# CIR_LED_SEQ.net
KiCad netlist of a schematic drawn in Altium Designer
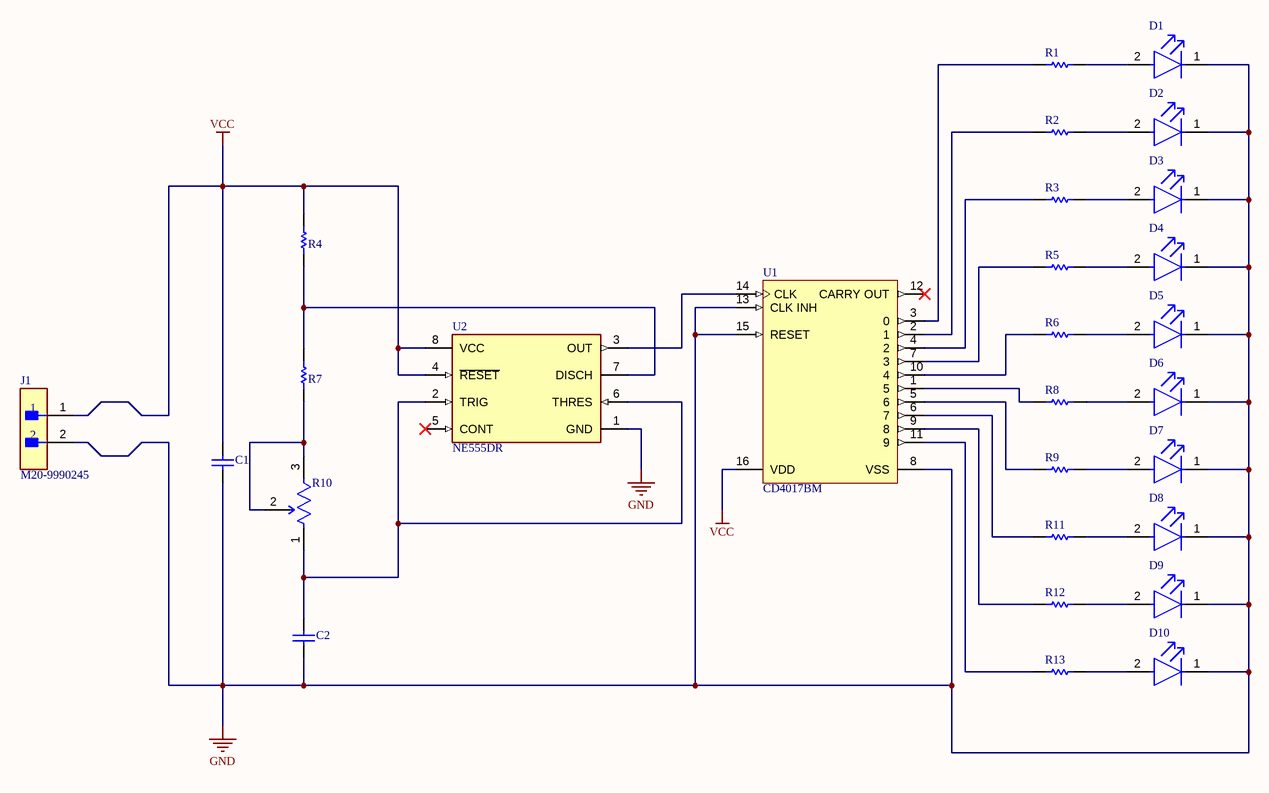
[diagram p0: CIR_LED_SEQ.SchDoc]

(export (version "E")
  (design (tool "Eeschema 10.0.6"))
  (components
    (comp (ref "C1")
      (value "1uf")
      (footprint "CAPC2013X135X45LL10T25")
      (fields (field (name "MANUFACTURER") "Murata") (field (name "PART NUMBER") "GRM21BR71H105KA12L"))
      (libsource (lib "Altium Content Vault") (part "CAP"))
    )
    (comp (ref "C2")
      (value "GRM21BR71H105KA12L")
      (footprint "CAPC2013X135X45LL10T25")
      (fields (field (name "MANUFACTURER") "Murata"))
      (libsource (lib "Altium Content Vault") (part "CAP"))
    )
    (comp (ref "D1")
      (value "HLMP-1719")
      (footprint "FP-HLMP-1719-MFG")
      (description "LED YELLOW DIFFUSED T-1 T/H")
      (fields
        (field (name "MANUFACTURER") "Broadcom")
        (field (name "OCTOPART") "https://octopart.com/hlmp-1719-broadcom-71130405")
      )
      (libsource (lib "Altium Content Vault") (part "8706943c75ba83719d021d2fdc84c58"))
    )
    (comp (ref "D2")
      (value "HLMP-1719")
      (footprint "FP-HLMP-1719-MFG")
      (description "LED YELLOW DIFFUSED T-1 T/H")
      (fields
        (field (name "MANUFACTURER") "Broadcom")
        (field (name "OCTOPART") "https://octopart.com/hlmp-1719-broadcom-71130405")
      )
      (libsource (lib "Altium Content Vault") (part "8706943c75ba83719d021d2fdc84c58"))
    )
    (comp (ref "D3")
      (value "HLMP-1719")
      (footprint "FP-HLMP-1719-MFG")
      (description "LED YELLOW DIFFUSED T-1 T/H")
      (fields
        (field (name "MANUFACTURER") "Broadcom")
        (field (name "OCTOPART") "https://octopart.com/hlmp-1719-broadcom-71130405")
      )
      (libsource (lib "Altium Content Vault") (part "8706943c75ba83719d021d2fdc84c58"))
    )
    (comp (ref "D4")
      (value "HLMP-1719")
      (footprint "FP-HLMP-1719-MFG")
      (description "LED YELLOW DIFFUSED T-1 T/H")
      (fields
        (field (name "MANUFACTURER") "Broadcom")
        (field (name "OCTOPART") "https://octopart.com/hlmp-1719-broadcom-71130405")
      )
      (libsource (lib "Altium Content Vault") (part "8706943c75ba83719d021d2fdc84c58"))
    )
    (comp (ref "D5")
      (value "HLMP-1719")
      (footprint "FP-HLMP-1719-MFG")
      (description "LED YELLOW DIFFUSED T-1 T/H")
      (fields
        (field (name "MANUFACTURER") "Broadcom")
        (field (name "OCTOPART") "https://octopart.com/hlmp-1719-broadcom-71130405")
      )
      (libsource (lib "Altium Content Vault") (part "8706943c75ba83719d021d2fdc84c58"))
    )
    (comp (ref "D6")
      (value "HLMP-1719")
      (footprint "FP-HLMP-1719-MFG")
      (description "LED YELLOW DIFFUSED T-1 T/H")
      (fields
        (field (name "MANUFACTURER") "Broadcom")
        (field (name "OCTOPART") "https://octopart.com/hlmp-1719-broadcom-71130405")
      )
      (libsource (lib "Altium Content Vault") (part "8706943c75ba83719d021d2fdc84c58"))
    )
    (comp (ref "D7")
      (value "HLMP-1719")
      (footprint "FP-HLMP-1719-MFG")
      (description "LED YELLOW DIFFUSED T-1 T/H")
      (fields
        (field (name "MANUFACTURER") "Broadcom")
        (field (name "OCTOPART") "https://octopart.com/hlmp-1719-broadcom-71130405")
      )
      (libsource (lib "Altium Content Vault") (part "8706943c75ba83719d021d2fdc84c58"))
    )
    (comp (ref "D8")
      (value "HLMP-1719")
      (footprint "FP-HLMP-1719-MFG")
      (description "LED YELLOW DIFFUSED T-1 T/H")
      (fields
        (field (name "MANUFACTURER") "Broadcom")
        (field (name "OCTOPART") "https://octopart.com/hlmp-1719-broadcom-71130405")
      )
      (libsource (lib "Altium Content Vault") (part "8706943c75ba83719d021d2fdc84c58"))
    )
    (comp (ref "D9")
      (value "HLMP-1719")
      (footprint "FP-HLMP-1719-MFG")
      (description "LED YELLOW DIFFUSED T-1 T/H")
      (fields
        (field (name "MANUFACTURER") "Broadcom")
        (field (name "OCTOPART") "https://octopart.com/hlmp-1719-broadcom-71130405")
      )
      (libsource (lib "Altium Content Vault") (part "8706943c75ba83719d021d2fdc84c58"))
    )
    (comp (ref "D10")
      (value "HLMP-1719")
      (footprint "FP-HLMP-1719-MFG")
      (description "LED YELLOW DIFFUSED T-1 T/H")
      (fields
        (field (name "MANUFACTURER") "Broadcom")
        (field (name "OCTOPART") "https://octopart.com/hlmp-1719-broadcom-71130405")
      )
      (libsource (lib "Altium Content Vault") (part "8706943c75ba83719d021d2fdc84c58"))
    )
    (comp (ref "J1")
      (value "M20-9990245")
      (footprint "FP-M20-9990245-MFG")
      (description "CONN HEADER VERT 2POS 2.54MM")
      (fields (field (name "VOLTAGE") "50V"))
      (libsource (lib "Altium Content Vault") (part "3bc925449376181038e59eaffc5286c"))
    )
    (comp (ref "R1")
      (value "RC0805FR-071KL")
      (footprint "RESC2013X60X35ML10T20")
      (description "Chip Resistor, 1 KOhm, +/- 1%, 125 mW, -55 to 155 degC, 0805 (2012 Metric), RoHS, Tape and Reel")
      (fields (field (name "TOLERANCE") "1%") (field (name "MANUFACTURER") "Yageo"))
      (libsource (lib "Altium Content Vault") (part "RES-2"))
    )
    (comp (ref "R2")
      (value "RC0805FR-071KL")
      (footprint "RESC2013X60X35ML10T20")
      (description "Chip Resistor, 1 KOhm, +/- 1%, 125 mW, -55 to 155 degC, 0805 (2012 Metric), RoHS, Tape and Reel")
      (fields (field (name "TOLERANCE") "1%") (field (name "MANUFACTURER") "Yageo"))
      (libsource (lib "Altium Content Vault") (part "RES-2"))
    )
    (comp (ref "R3")
      (value "RC0805FR-071KL")
      (footprint "RESC2013X60X35ML10T20")
      (description "Chip Resistor, 1 KOhm, +/- 1%, 125 mW, -55 to 155 degC, 0805 (2012 Metric), RoHS, Tape and Reel")
      (fields (field (name "TOLERANCE") "1%") (field (name "MANUFACTURER") "Yageo"))
      (libsource (lib "Altium Content Vault") (part "RES-2"))
    )
    (comp (ref "R4")
      (value "2k2")
      (footprint "RESC2013X60X35ML10T20")
      (description "Chip Resistor, 1 KOhm, +/- 1%, 125 mW, -55 to 155 degC, 0805 (2012 Metric), RoHS, Tape and Reel")
      (fields (field (name "TOLERANCE") "1%") (field (name "MANUFACTURER") "Yageo"))
      (libsource (lib "Altium Content Vault") (part "RES-2"))
    )
    (comp (ref "R5")
      (value "RC0805FR-071KL")
      (footprint "RESC2013X60X35ML10T20")
      (description "Chip Resistor, 1 KOhm, +/- 1%, 125 mW, -55 to 155 degC, 0805 (2012 Metric), RoHS, Tape and Reel")
      (fields (field (name "TOLERANCE") "1%") (field (name "MANUFACTURER") "Yageo"))
      (libsource (lib "Altium Content Vault") (part "RES-2"))
    )
    (comp (ref "R6")
      (value "RC0805FR-071KL")
      (footprint "RESC2013X60X35ML10T20")
      (description "Chip Resistor, 1 KOhm, +/- 1%, 125 mW, -55 to 155 degC, 0805 (2012 Metric), RoHS, Tape and Reel")
      (fields (field (name "TOLERANCE") "1%") (field (name "MANUFACTURER") "Yageo"))
      (libsource (lib "Altium Content Vault") (part "RES-2"))
    )
    (comp (ref "R7")
      (value "10k")
      (footprint "RESC2013X60X35ML10T20")
      (description "Chip Resistor, 1 KOhm, +/- 1%, 125 mW, -55 to 155 degC, 0805 (2012 Metric), RoHS, Tape and Reel")
      (fields (field (name "TOLERANCE") "1%") (field (name "MANUFACTURER") "Yageo"))
      (libsource (lib "Altium Content Vault") (part "RES-2"))
    )
    (comp (ref "R8")
      (value "RC0805FR-071KL")
      (footprint "RESC2013X60X35ML10T20")
      (description "Chip Resistor, 1 KOhm, +/- 1%, 125 mW, -55 to 155 degC, 0805 (2012 Metric), RoHS, Tape and Reel")
      (fields (field (name "TOLERANCE") "1%") (field (name "MANUFACTURER") "Yageo"))
      (libsource (lib "Altium Content Vault") (part "RES-2"))
    )
    (comp (ref "R9")
      (value "RC0805FR-071KL")
      (footprint "RESC2013X60X35ML10T20")
      (description "Chip Resistor, 1 KOhm, +/- 1%, 125 mW, -55 to 155 degC, 0805 (2012 Metric), RoHS, Tape and Reel")
      (fields (field (name "TOLERANCE") "1%") (field (name "MANUFACTURER") "Yageo"))
      (libsource (lib "Altium Content Vault") (part "RES-2"))
    )
    (comp (ref "R10")
      (value "50k")
      (footprint "FP-3386P-MFG")
      (description "TRIMMER 100K OHM 0.5W PC PIN TOP")
      (fields (field (name "TOLERANCE") "10%"))
      (libsource (lib "Altium Content Vault") (part "13357d81287629c2fd191d242cfa50c"))
    )
    (comp (ref "R11")
      (value "RC0805FR-071KL")
      (footprint "RESC2013X60X35ML10T20")
      (description "Chip Resistor, 1 KOhm, +/- 1%, 125 mW, -55 to 155 degC, 0805 (2012 Metric), RoHS, Tape and Reel")
      (fields (field (name "TOLERANCE") "1%") (field (name "MANUFACTURER") "Yageo"))
      (libsource (lib "Altium Content Vault") (part "RES-2"))
    )
    (comp (ref "R12")
      (value "RC0805FR-071KL")
      (footprint "RESC2013X60X35ML10T20")
      (description "Chip Resistor, 1 KOhm, +/- 1%, 125 mW, -55 to 155 degC, 0805 (2012 Metric), RoHS, Tape and Reel")
      (fields (field (name "TOLERANCE") "1%") (field (name "MANUFACTURER") "Yageo"))
      (libsource (lib "Altium Content Vault") (part "RES-2"))
    )
    (comp (ref "R13")
      (value "RC0805FR-071KL")
      (footprint "RESC2013X60X35ML10T20")
      (description "Chip Resistor, 1 KOhm, +/- 1%, 125 mW, -55 to 155 degC, 0805 (2012 Metric), RoHS, Tape and Reel")
      (fields (field (name "TOLERANCE") "1%") (field (name "MANUFACTURER") "Yageo"))
      (libsource (lib "Altium Content Vault") (part "RES-2"))
    )
    (comp (ref "U1")
      (value "CD4017BM")
      (footprint "D0016A_N")
      (description "CMOS Decade Counter with 10 Decoded Outputs, D0016A, TUBE")
      (fields
        (field (name "GENERIC PART NUMBER") "CD4017B")
        (field (name "MANUFACTURER") "Texas Instruments")
      )
      (libsource (lib "Altium Content Vault") (part "TI-CD4017B-16"))
    )
    (comp (ref "U2")
      (value "NE555DR")
      (footprint "FP-D0008A-IPC_A")
      (description "IC OSC SGL TIMER 100KHZ 8-SOIC")
      (libsource (lib "Altium Content Vault") (part "a29bba90211dec1890110b94dad7d53"))
    )
  )
  (nets
    (net (code "1") (name "GND") (class "Default")
      (node (ref "C1") (pin "1") (pinfunction "1_1") (pintype "passive"))
      (node (ref "C2") (pin "1") (pinfunction "1_1") (pintype "passive"))
      (node (ref "D1") (pin "1") (pinfunction "C_1") (pintype "passive"))
      (node (ref "D10") (pin "1") (pinfunction "C_1") (pintype "passive"))
      (node (ref "D2") (pin "1") (pinfunction "C_1") (pintype "passive"))
      (node (ref "D3") (pin "1") (pinfunction "C_1") (pintype "passive"))
      (node (ref "D4") (pin "1") (pinfunction "C_1") (pintype "passive"))
      (node (ref "D5") (pin "1") (pinfunction "C_1") (pintype "passive"))
      (node (ref "D6") (pin "1") (pinfunction "C_1") (pintype "passive"))
      (node (ref "D7") (pin "1") (pinfunction "C_1") (pintype "passive"))
      (node (ref "D8") (pin "1") (pinfunction "C_1") (pintype "passive"))
      (node (ref "D9") (pin "1") (pinfunction "C_1") (pintype "passive"))
      (node (ref "J1") (pin "2") (pinfunction "2_2") (pintype "passive"))
      (node (ref "U1") (pin "13") (pinfunction "CLK_INH_13") (pintype "input"))
      (node (ref "U1") (pin "15") (pinfunction "RESET_15") (pintype "input"))
      (node (ref "U1") (pin "8") (pinfunction "VSS_8") (pintype "power_in"))
      (node (ref "U2") (pin "1") (pinfunction "GND_1") (pintype "power_in"))
    )
    (net (code "2") (name "Net-(D1-A)") (class "Default")
      (node (ref "D1") (pin "2") (pinfunction "A_2") (pintype "passive"))
      (node (ref "R1") (pin "2") (pinfunction "2_2") (pintype "passive"))
    )
    (net (code "3") (name "Net-(D2-A)") (class "Default")
      (node (ref "D2") (pin "2") (pinfunction "A_2") (pintype "passive"))
      (node (ref "R2") (pin "2") (pinfunction "2_2") (pintype "passive"))
    )
    (net (code "4") (name "Net-(D3-A)") (class "Default")
      (node (ref "D3") (pin "2") (pinfunction "A_2") (pintype "passive"))
      (node (ref "R3") (pin "2") (pinfunction "2_2") (pintype "passive"))
    )
    (net (code "5") (name "Net-(D4-A)") (class "Default")
      (node (ref "D4") (pin "2") (pinfunction "A_2") (pintype "passive"))
      (node (ref "R5") (pin "2") (pinfunction "2_2") (pintype "passive"))
    )
    (net (code "6") (name "Net-(D5-A)") (class "Default")
      (node (ref "D5") (pin "2") (pinfunction "A_2") (pintype "passive"))
      (node (ref "R6") (pin "2") (pinfunction "2_2") (pintype "passive"))
    )
    (net (code "7") (name "Net-(D6-A)") (class "Default")
      (node (ref "D6") (pin "2") (pinfunction "A_2") (pintype "passive"))
      (node (ref "R8") (pin "2") (pinfunction "2_2") (pintype "passive"))
    )
    (net (code "8") (name "Net-(D7-A)") (class "Default")
      (node (ref "D7") (pin "2") (pinfunction "A_2") (pintype "passive"))
      (node (ref "R9") (pin "2") (pinfunction "2_2") (pintype "passive"))
    )
    (net (code "9") (name "Net-(D8-A)") (class "Default")
      (node (ref "D8") (pin "2") (pinfunction "A_2") (pintype "passive"))
      (node (ref "R11") (pin "2") (pinfunction "2_2") (pintype "passive"))
    )
    (net (code "10") (name "Net-(D9-A)") (class "Default")
      (node (ref "D9") (pin "2") (pinfunction "A_2") (pintype "passive"))
      (node (ref "R12") (pin "2") (pinfunction "2_2") (pintype "passive"))
    )
    (net (code "11") (name "Net-(D10-A)") (class "Default")
      (node (ref "D10") (pin "2") (pinfunction "A_2") (pintype "passive"))
      (node (ref "R13") (pin "2") (pinfunction "2_2") (pintype "passive"))
    )
    (net (code "12") (name "Net-(R10-CCW)") (class "Default")
      (node (ref "C2") (pin "2") (pinfunction "2_2") (pintype "passive"))
      (node (ref "R10") (pin "1") (pinfunction "CCW_1") (pintype "passive"))
      (node (ref "U2") (pin "2") (pinfunction "TRIG_2") (pintype "input"))
      (node (ref "U2") (pin "6") (pinfunction "THRES_6") (pintype "input"))
    )
    (net (code "13") (name "Net-(R10-CW)") (class "Default")
      (node (ref "R10") (pin "2") (pinfunction "WIPER_2") (pintype "passive"))
      (node (ref "R10") (pin "3") (pinfunction "CW_3") (pintype "passive"))
      (node (ref "R7") (pin "1") (pinfunction "1_1") (pintype "passive"))
    )
    (net (code "14") (name "Net-(U1-0)") (class "Default")
      (node (ref "R1") (pin "1") (pinfunction "1_1") (pintype "passive"))
      (node (ref "U1") (pin "3") (pinfunction "0_3") (pintype "output"))
    )
    (net (code "15") (name "Net-(U1-1)") (class "Default")
      (node (ref "R2") (pin "1") (pinfunction "1_1") (pintype "passive"))
      (node (ref "U1") (pin "2") (pinfunction "1_2") (pintype "output"))
    )
    (net (code "16") (name "Net-(U1-2)") (class "Default")
      (node (ref "R3") (pin "1") (pinfunction "1_1") (pintype "passive"))
      (node (ref "U1") (pin "4") (pinfunction "2_4") (pintype "output"))
    )
    (net (code "17") (name "Net-(U1-3)") (class "Default")
      (node (ref "R5") (pin "1") (pinfunction "1_1") (pintype "passive"))
      (node (ref "U1") (pin "7") (pinfunction "3_7") (pintype "output"))
    )
    (net (code "18") (name "Net-(U1-4)") (class "Default")
      (node (ref "R6") (pin "1") (pinfunction "1_1") (pintype "passive"))
      (node (ref "U1") (pin "10") (pinfunction "4_10") (pintype "output"))
    )
    (net (code "19") (name "Net-(U1-5)") (class "Default")
      (node (ref "R8") (pin "1") (pinfunction "1_1") (pintype "passive"))
      (node (ref "U1") (pin "1") (pinfunction "5_1") (pintype "output"))
    )
    (net (code "20") (name "Net-(U1-6)") (class "Default")
      (node (ref "R9") (pin "1") (pinfunction "1_1") (pintype "passive"))
      (node (ref "U1") (pin "5") (pinfunction "6_5") (pintype "output"))
    )
    (net (code "21") (name "Net-(U1-7)") (class "Default")
      (node (ref "R11") (pin "1") (pinfunction "1_1") (pintype "passive"))
      (node (ref "U1") (pin "6") (pinfunction "7_6") (pintype "output"))
    )
    (net (code "22") (name "Net-(U1-8)") (class "Default")
      (node (ref "R12") (pin "1") (pinfunction "1_1") (pintype "passive"))
      (node (ref "U1") (pin "9") (pinfunction "8_9") (pintype "output"))
    )
    (net (code "23") (name "Net-(U1-9)") (class "Default")
      (node (ref "R13") (pin "1") (pinfunction "1_1") (pintype "passive"))
      (node (ref "U1") (pin "11") (pinfunction "9_11") (pintype "output"))
    )
    (net (code "24") (name "Net-(U1-CLK)") (class "Default")
      (node (ref "U1") (pin "14") (pinfunction "CLK_14") (pintype "input"))
      (node (ref "U2") (pin "3") (pinfunction "OUT_3") (pintype "output"))
    )
    (net (code "25") (name "Net-(U2-DISCH)") (class "Default")
      (node (ref "R4") (pin "1") (pinfunction "1_1") (pintype "passive"))
      (node (ref "R7") (pin "2") (pinfunction "2_2") (pintype "passive"))
      (node (ref "U2") (pin "7") (pinfunction "DISCH_7") (pintype "open_collector"))
    )
    (net (code "26") (name "VCC") (class "Default")
      (node (ref "C1") (pin "2") (pinfunction "2_2") (pintype "passive"))
      (node (ref "J1") (pin "1") (pinfunction "1_1") (pintype "passive"))
      (node (ref "R4") (pin "2") (pinfunction "2_2") (pintype "passive"))
      (node (ref "U1") (pin "16") (pinfunction "VDD_16") (pintype "power_in"))
      (node (ref "U2") (pin "4") (pinfunction "~{RESET}_4") (pintype "input"))
      (node (ref "U2") (pin "8") (pinfunction "VCC_8") (pintype "power_in"))
    )
    (net (code "27") (name "unconnected-(U1-CARRY_OUT-Pad12)") (class "Default")
      (node (ref "U1") (pin "12") (pinfunction "CARRY_OUT_12") (pintype "output+no_connect"))
    )
    (net (code "28") (name "unconnected-(U2-CONT-Pad5)") (class "Default")
      (node (ref "U2") (pin "5") (pinfunction "CONT_5") (pintype "input+no_connect"))
    )
  )
)
